# PCB_Accessoire_Puissance_ED0B.net
KiCad netlist of a schematic drawn in EAGLE
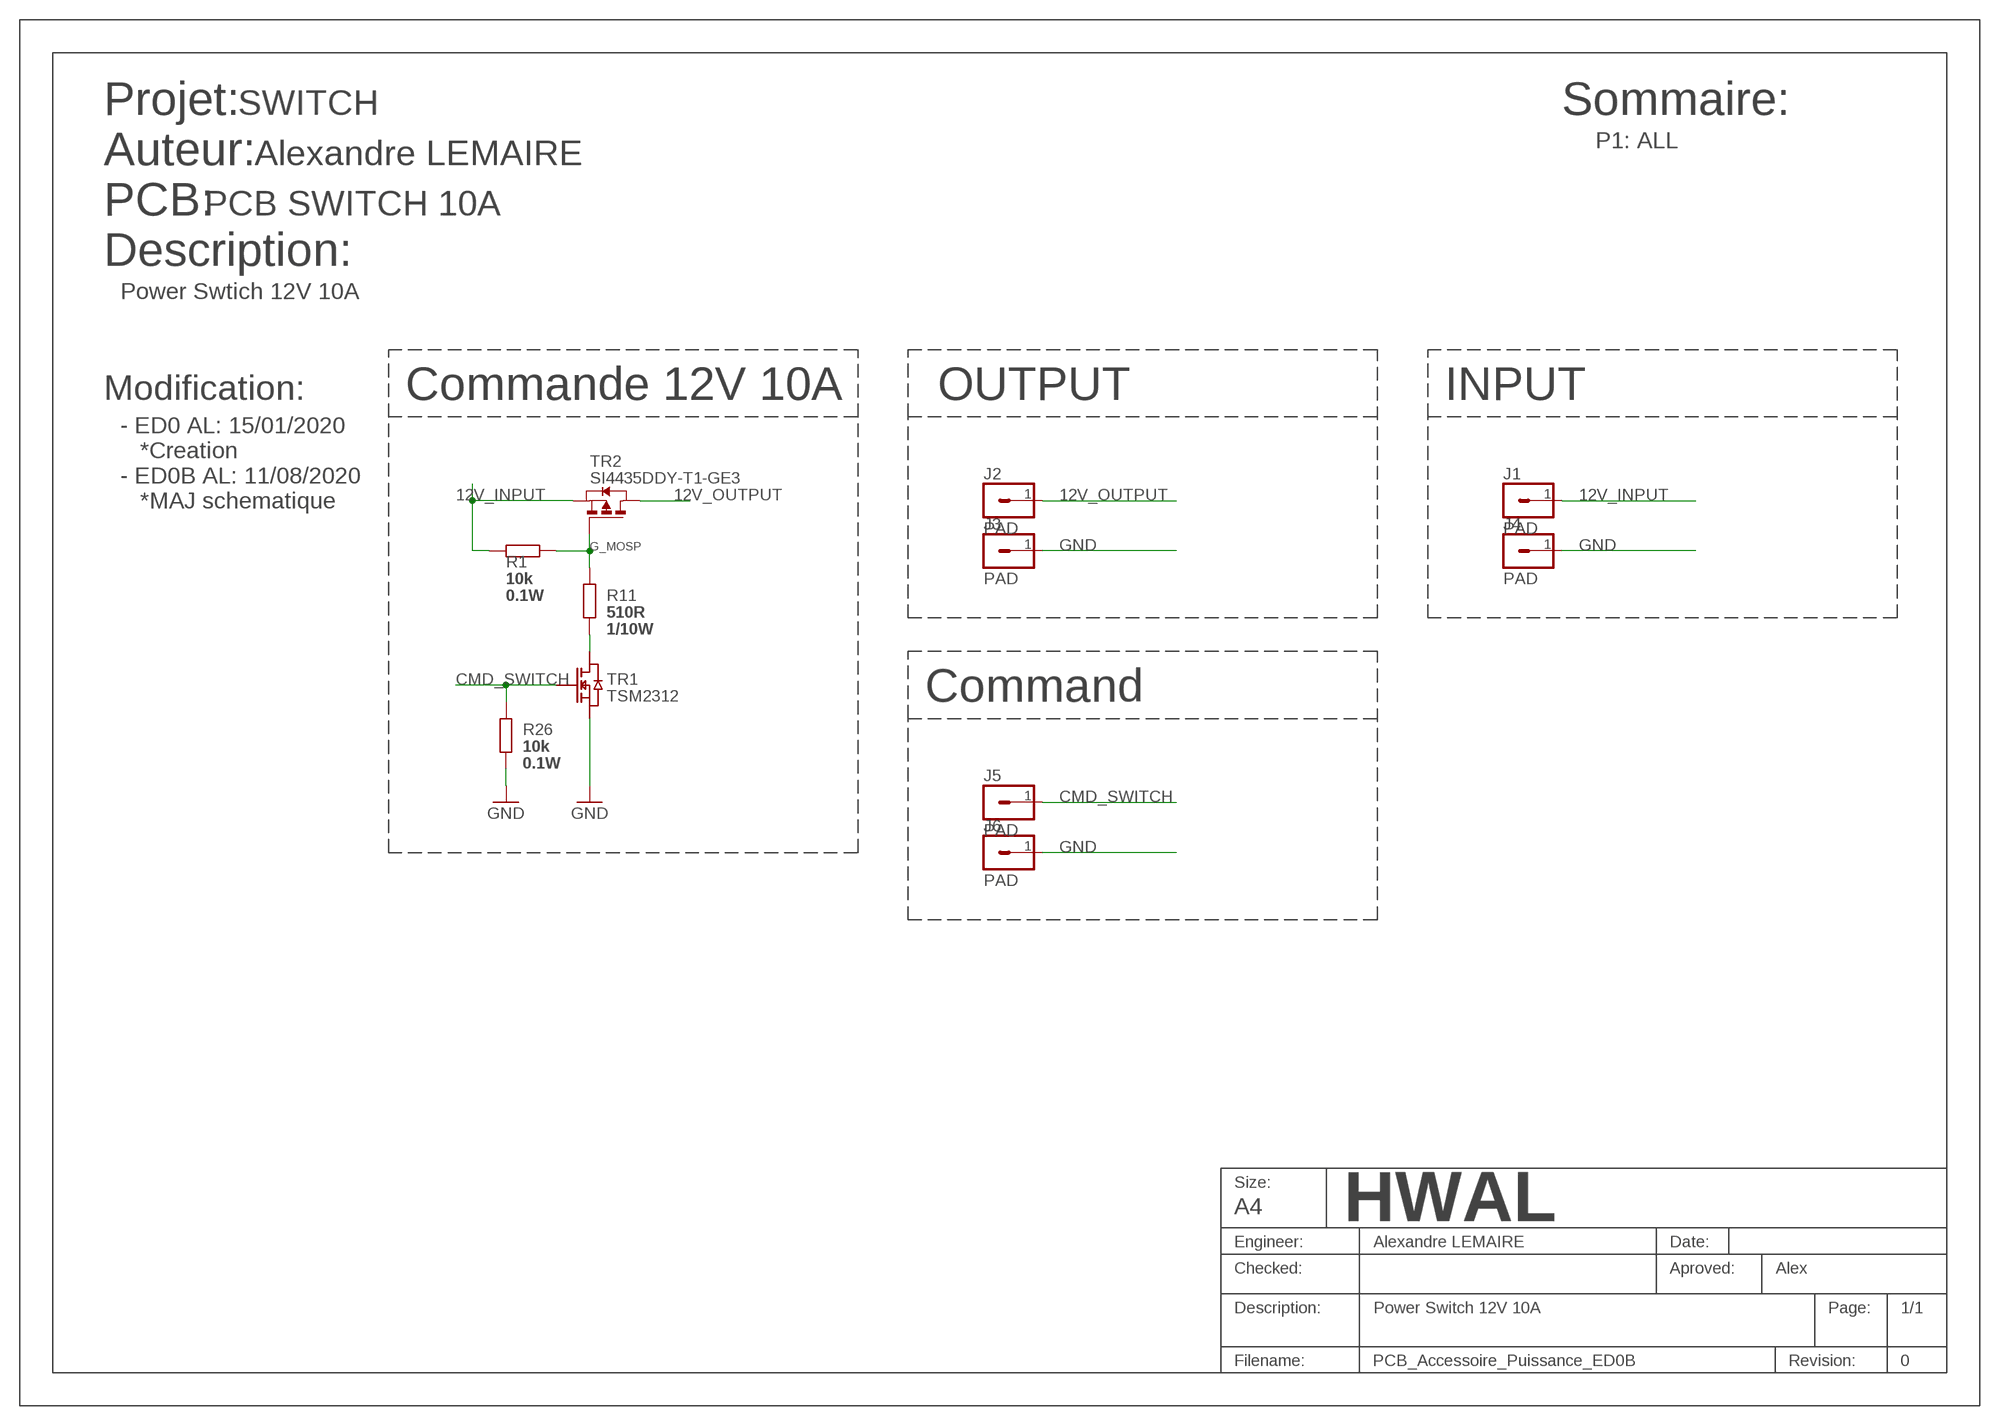
[diagram p0: schematic, sheet 1]

(export (version "E")
  (design (tool "Eeschema 10.0.6"))
  (components
    (comp (ref "J1")
      (value "PAD")
      (footprint "eagle-import:PAD_2X3MM")
      (libsource (lib "eagle-import") (part "PLOT-1-2X3MM"))
    )
    (comp (ref "J2")
      (value "PAD")
      (footprint "eagle-import:PAD_2X3MM")
      (libsource (lib "eagle-import") (part "PLOT-1-2X3MM"))
    )
    (comp (ref "J3")
      (value "PAD")
      (footprint "eagle-import:PAD_2X3MM")
      (libsource (lib "eagle-import") (part "PLOT-1-2X3MM"))
    )
    (comp (ref "J4")
      (value "PAD")
      (footprint "eagle-import:PAD_2X3MM")
      (libsource (lib "eagle-import") (part "PLOT-1-2X3MM"))
    )
    (comp (ref "J5")
      (value "PAD")
      (footprint "eagle-import:PAD_2X3MM")
      (libsource (lib "eagle-import") (part "PLOT-1-2X3MM"))
    )
    (comp (ref "J6")
      (value "PAD")
      (footprint "eagle-import:PAD_2X3MM")
      (libsource (lib "eagle-import") (part "PLOT-1-2X3MM"))
    )
    (comp (ref "R1")
      (value "10k")
      (footprint "eagle-import:R0603")
      (fields (field (name "POWER") "0.1W") (field (name "MF") "MULITCOMP"))
      (libsource (lib "eagle-import") (part "RE_10KR_1%_0.1W_0603_50V_A"))
    )
    (comp (ref "R11")
      (value "510R")
      (footprint "eagle-import:R0603")
      (fields (field (name "POWER") "1/10W") (field (name "MF") "YAGEO"))
      (libsource (lib "eagle-import") (part "RC_510R_1%_0.1W_0603"))
    )
    (comp (ref "R26")
      (value "10k")
      (footprint "eagle-import:R0603")
      (fields (field (name "POWER") "0.1W") (field (name "MF") "MULITCOMP"))
      (libsource (lib "eagle-import") (part "RE_10KR_1%_0.1W_0603_50V_A"))
    )
    (comp (ref "TR1")
      (value "TSM2312")
      (footprint "eagle-import:SOT23")
      (fields (field (name "MF") "Taiwan Semiconductor"))
      (libsource (lib "eagle-import") (part "MOS_N_20V_5A_0.033W_SOT23"))
    )
    (comp (ref "TR2")
      (value "SI4435DDY-T1-GE3")
      (footprint "eagle-import:SOIC8")
      (fields (field (name "MF") "Vishay"))
      (libsource (lib "eagle-import") (part "MOS_P_-30V_-10A_0,035OHM_SOIC8"))
    )
  )
  (nets
    (net (code "1") (name "/12V_INPUT") (class "Default")
      (node (ref "J1") (pin "1") (pinfunction "1_1") (pintype "passive"))
      (node (ref "R1") (pin "2") (pinfunction "2_2") (pintype "passive"))
      (node (ref "TR2") (pin "1") (pinfunction "S_1") (pintype "passive"))
      (node (ref "TR2") (pin "2") (pinfunction "S_2") (pintype "passive"))
      (node (ref "TR2") (pin "3") (pinfunction "S_3") (pintype "passive"))
    )
    (net (code "2") (name "/12V_OUTPUT") (class "Default")
      (node (ref "J2") (pin "1") (pinfunction "1_1") (pintype "passive"))
      (node (ref "TR2") (pin "5") (pinfunction "D_5") (pintype "passive"))
      (node (ref "TR2") (pin "6") (pinfunction "D_6") (pintype "passive"))
      (node (ref "TR2") (pin "7") (pinfunction "D_7") (pintype "passive"))
      (node (ref "TR2") (pin "8") (pinfunction "D_8") (pintype "passive"))
    )
    (net (code "3") (name "/CMD_SWITCH") (class "Default")
      (node (ref "J5") (pin "1") (pinfunction "1_1") (pintype "passive"))
      (node (ref "R26") (pin "2") (pinfunction "2_2") (pintype "passive"))
      (node (ref "TR1") (pin "1") (pinfunction "G_1") (pintype "bidirectional"))
    )
    (net (code "4") (name "/G_MOSP") (class "Default")
      (node (ref "R1") (pin "1") (pinfunction "1_1") (pintype "passive"))
      (node (ref "R11") (pin "2") (pinfunction "2_2") (pintype "passive"))
      (node (ref "TR2") (pin "4") (pinfunction "G_4") (pintype "passive"))
    )
    (net (code "5") (name "GND") (class "Default")
      (node (ref "J3") (pin "1") (pinfunction "1_1") (pintype "passive"))
      (node (ref "J4") (pin "1") (pinfunction "1_1") (pintype "passive"))
      (node (ref "J6") (pin "1") (pinfunction "1_1") (pintype "passive"))
      (node (ref "R26") (pin "1") (pinfunction "1_1") (pintype "passive"))
      (node (ref "TR1") (pin "2") (pinfunction "S_2") (pintype "bidirectional"))
    )
    (net (code "6") (name "Net-(TR1-D)") (class "Default")
      (node (ref "R11") (pin "1") (pinfunction "1_1") (pintype "passive"))
      (node (ref "TR1") (pin "3") (pinfunction "D_3") (pintype "bidirectional"))
    )
  )
)
